# reader_breakout.net
KiCad netlist of a schematic drawn in EAGLE
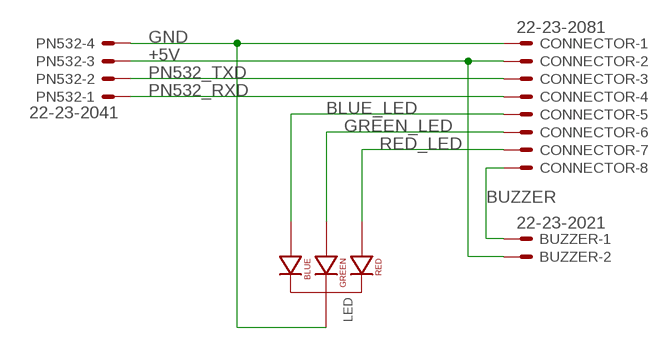
[diagram p0: schematic, sheet 1]

(export (version "E")
  (design (tool "Eeschema 10.0.6"))
  (components
    (comp (ref "BUZZER")
      (value "22-23-2021")
      (footprint "eagle-import:22-23-2021")
      (fields (field (name "MF") "MOLEX"))
      (libsource (lib "eagle-import") (part "22-23-2021"))
    )
    (comp (ref "CONNECTOR")
      (value "22-23-2081")
      (footprint "eagle-import:22-23-2081")
      (fields (field (name "MF") "MOLEX"))
      (libsource (lib "eagle-import") (part "22-23-2081"))
    )
    (comp (ref "LED")
      (value "LED-RGB-CC-THRUCLEAR")
      (footprint "eagle-import:LED-RGB-THRU")
      (libsource (lib "eagle-import") (part "LED-RGB-CC-THRUCLEAR"))
    )
    (comp (ref "PN532")
      (value "22-23-2041")
      (footprint "eagle-import:22-23-2041")
      (fields (field (name "MF") "MOLEX"))
      (libsource (lib "eagle-import") (part "22-23-2041"))
    )
  )
  (nets
    (net (code "1") (name "/+5V") (class "Default")
      (node (ref "BUZZER") (pin "2") (pinfunction "S_2") (pintype "passive"))
      (node (ref "CONNECTOR") (pin "2") (pinfunction "S_2") (pintype "passive"))
      (node (ref "PN532") (pin "3") (pinfunction "S_3") (pintype "passive"))
    )
    (net (code "2") (name "/BLUE_LED") (class "Default")
      (node (ref "CONNECTOR") (pin "5") (pinfunction "S_5") (pintype "passive"))
      (node (ref "LED") (pin "4") (pinfunction "BLUE_CATHODE_4") (pintype "bidirectional"))
    )
    (net (code "3") (name "/BUZZER") (class "Default")
      (node (ref "BUZZER") (pin "1") (pinfunction "S_1") (pintype "passive"))
      (node (ref "CONNECTOR") (pin "8") (pinfunction "S_8") (pintype "passive"))
    )
    (net (code "4") (name "/GND") (class "Default")
      (node (ref "CONNECTOR") (pin "1") (pinfunction "S_1") (pintype "passive"))
      (node (ref "LED") (pin "2") (pinfunction "CATHODE_2") (pintype "bidirectional"))
      (node (ref "PN532") (pin "4") (pinfunction "S_4") (pintype "passive"))
    )
    (net (code "5") (name "/GREEN_LED") (class "Default")
      (node (ref "CONNECTOR") (pin "6") (pinfunction "S_6") (pintype "passive"))
      (node (ref "LED") (pin "3") (pinfunction "GREEN_CATHODE_3") (pintype "bidirectional"))
    )
    (net (code "6") (name "/PN532_RXD") (class "Default")
      (node (ref "CONNECTOR") (pin "4") (pinfunction "S_4") (pintype "passive"))
      (node (ref "PN532") (pin "1") (pinfunction "S_1") (pintype "passive"))
    )
    (net (code "7") (name "/PN532_TXD") (class "Default")
      (node (ref "CONNECTOR") (pin "3") (pinfunction "S_3") (pintype "passive"))
      (node (ref "PN532") (pin "2") (pinfunction "S_2") (pintype "passive"))
    )
    (net (code "8") (name "/RED_LED") (class "Default")
      (node (ref "CONNECTOR") (pin "7") (pinfunction "S_7") (pintype "passive"))
      (node (ref "LED") (pin "1") (pinfunction "RED_CATHODE_1") (pintype "bidirectional"))
    )
  )
)
